# LiPoCharger.net
KiCad netlist of a schematic drawn in EAGLE
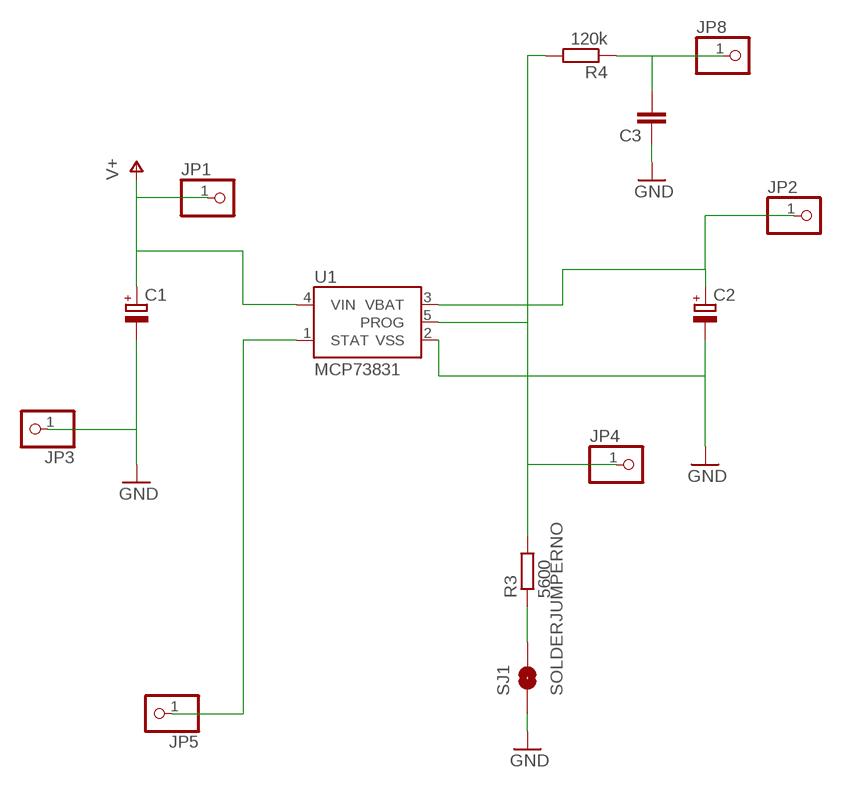
[diagram p0: schematic, sheet 1]

(export (version "E")
  (design (tool "Eeschema 10.0.6"))
  (components
    (comp (ref "C1")
      (value "CPOL-EUE2.5-6")
      (footprint "eagle-import:E2,5-6")
      (libsource (lib "eagle-import") (part "CPOL-EUE2.5-6"))
    )
    (comp (ref "C2")
      (value "CPOL-EUE2.5-6")
      (footprint "eagle-import:E2,5-6")
      (libsource (lib "eagle-import") (part "CPOL-EUE2.5-6"))
    )
    (comp (ref "C3")
      (value "C-EUC1206")
      (footprint "eagle-import:C1206")
      (libsource (lib "eagle-import") (part "C-EUC1206"))
    )
    (comp (ref "JP1")
      (value "PINHD-1X1")
      (footprint "eagle-import:1X01")
      (libsource (lib "eagle-import") (part "PINHD-1X1"))
    )
    (comp (ref "JP2")
      (value "PINHD-1X1")
      (footprint "eagle-import:1X01")
      (libsource (lib "eagle-import") (part "PINHD-1X1"))
    )
    (comp (ref "JP3")
      (value "PINHD-1X1")
      (footprint "eagle-import:1X01")
      (libsource (lib "eagle-import") (part "PINHD-1X1"))
    )
    (comp (ref "JP4")
      (value "PINHD-1X1")
      (footprint "eagle-import:1X01")
      (libsource (lib "eagle-import") (part "PINHD-1X1"))
    )
    (comp (ref "JP5")
      (value "PINHD-1X1")
      (footprint "eagle-import:1X01")
      (libsource (lib "eagle-import") (part "PINHD-1X1"))
    )
    (comp (ref "JP8")
      (value "PINHD-1X1")
      (footprint "eagle-import:1X01")
      (libsource (lib "eagle-import") (part "PINHD-1X1"))
    )
    (comp (ref "R3")
      (value "5600")
      (footprint "eagle-import:R0402")
      (libsource (lib "eagle-import") (part "R-EU_R0402"))
    )
    (comp (ref "R4")
      (value "120k")
      (footprint "eagle-import:R0402")
      (libsource (lib "eagle-import") (part "R-EU_R0402"))
    )
    (comp (ref "SJ1")
      (value "SOLDERJUMPERNO")
      (footprint "eagle-import:SJ_2S-NO")
      (libsource (lib "eagle-import") (part "SOLDERJUMPERNO"))
    )
    (comp (ref "U1")
      (value "MCP73831")
      (footprint "eagle-import:SOT23-5")
      (libsource (lib "eagle-import") (part "MCP73831"))
    )
  )
  (nets
    (net (code "1") (name "GND") (class "Default")
      (node (ref "C1") (pin "-") (pinfunction "-_-") (pintype "passive"))
      (node (ref "C2") (pin "-") (pinfunction "-_-") (pintype "passive"))
      (node (ref "C3") (pin "1") (pinfunction "1_1") (pintype "passive"))
      (node (ref "JP3") (pin "1") (pinfunction "1_1") (pintype "passive"))
      (node (ref "SJ1") (pin "1") (pinfunction "1_1") (pintype "passive"))
      (node (ref "U1") (pin "2") (pinfunction "VSS_2") (pintype "power_in"))
    )
    (net (code "2") (name "Net-(C3-Pad2)") (class "Default")
      (node (ref "C3") (pin "2") (pinfunction "2_2") (pintype "passive"))
      (node (ref "JP8") (pin "1") (pinfunction "1_1") (pintype "passive"))
      (node (ref "R4") (pin "1") (pinfunction "1_1") (pintype "passive"))
    )
    (net (code "3") (name "Net-(R3-Pad1)") (class "Default")
      (node (ref "R3") (pin "1") (pinfunction "1_1") (pintype "passive"))
      (node (ref "SJ1") (pin "2") (pinfunction "2_2") (pintype "passive"))
    )
    (net (code "4") (name "Net-(U1-PROG)") (class "Default")
      (node (ref "JP4") (pin "1") (pinfunction "1_1") (pintype "passive"))
      (node (ref "R3") (pin "2") (pinfunction "2_2") (pintype "passive"))
      (node (ref "R4") (pin "2") (pinfunction "2_2") (pintype "passive"))
      (node (ref "U1") (pin "5") (pinfunction "PROG_5") (pintype "input"))
    )
    (net (code "5") (name "Net-(U1-STAT)") (class "Default")
      (node (ref "JP5") (pin "1") (pinfunction "1_1") (pintype "passive"))
      (node (ref "U1") (pin "1") (pinfunction "STAT_1") (pintype "output"))
    )
    (net (code "6") (name "Net-(U1-VBAT)") (class "Default")
      (node (ref "C2") (pin "+") (pinfunction "+_+") (pintype "passive"))
      (node (ref "JP2") (pin "1") (pinfunction "1_1") (pintype "passive"))
      (node (ref "U1") (pin "3") (pinfunction "VBAT_3") (pintype "power_in"))
    )
    (net (code "7") (name "V+") (class "Default")
      (node (ref "C1") (pin "+") (pinfunction "+_+") (pintype "passive"))
      (node (ref "JP1") (pin "1") (pinfunction "1_1") (pintype "passive"))
      (node (ref "U1") (pin "4") (pinfunction "VIN_4") (pintype "power_in"))
    )
  )
)
